# ID_VD.net
KiCad netlist of a schematic drawn in Altium Designer
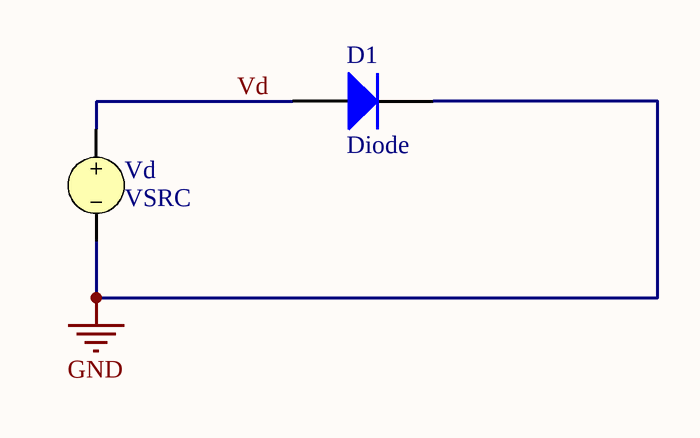
[diagram p0: ID_VD.SchDoc]

(export (version "E")
  (design (tool "Eeschema 10.0.6"))
  (components
    (comp (ref "D1")
      (value "Diode")
      (footprint "SMC")
      (description "Default Diode")
      (fields (field (name "PUBLISHER") "Altium Limited"))
      (libsource (lib "Miscellaneous Devices") (part "Diode"))
    )
    (comp (ref "Vd")
      (value "VSRC")
      (description "Voltage Source")
      (fields (field (name "PUBLISHER") "Altium Limited"))
      (libsource (lib "Simulation Sources") (part "VSRC"))
    )
  )
  (nets
    (net (code "1") (name "/Vd") (class "Default")
      (node (ref "D1") (pin "1") (pinfunction "A_1") (pintype "passive"))
      (node (ref "Vd") (pin "1") (pinfunction "1_1") (pintype "passive"))
    )
    (net (code "2") (name "GND") (class "Default")
      (node (ref "D1") (pin "2") (pinfunction "K_2") (pintype "passive"))
      (node (ref "Vd") (pin "2") (pinfunction "2_2") (pintype "passive"))
    )
  )
)
